# XDS_100_USB_Programmer.net
KiCad netlist of a schematic drawn in Altium Designer
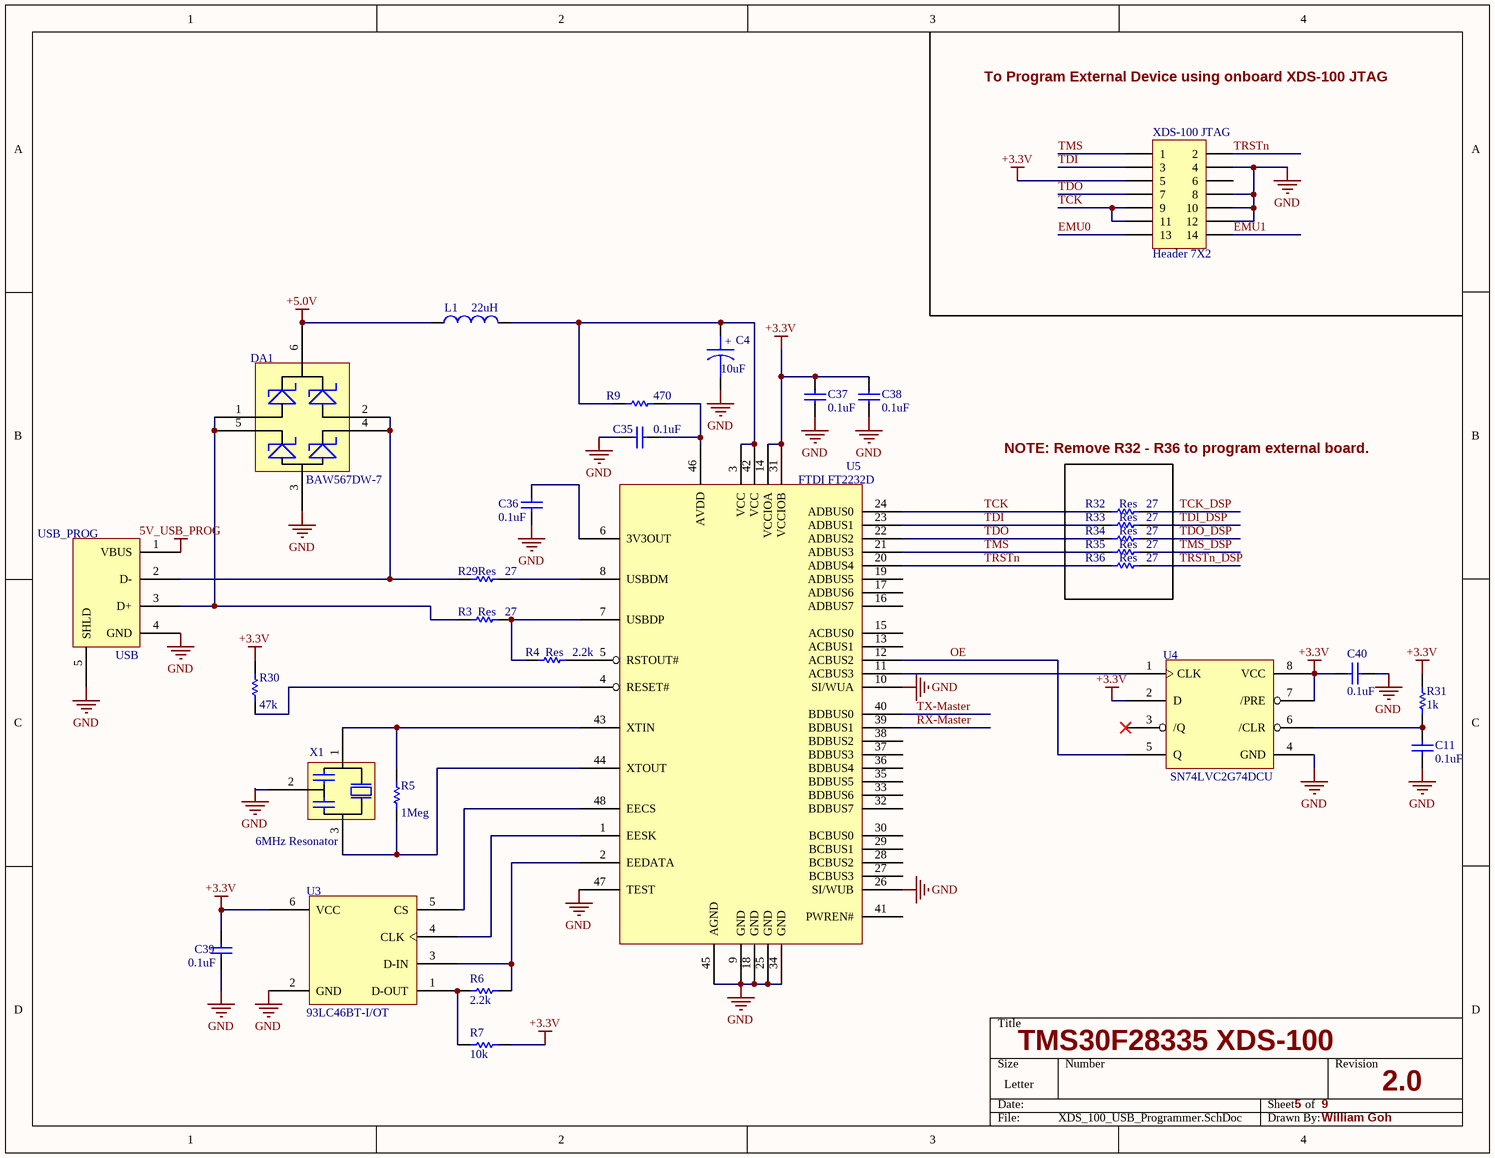
[diagram p0: XDS_100_USB_Programmer.SchDoc]

(export (version "E")
  (design (tool "Eeschema 10.0.6"))
  (components
    (comp (ref "C4")
      (value "10uF")
      (footprint "3528")
      (description "Capacitor Tantalum")
      (fields (field (name "Comment") "Pol Cap"))
      (libsource (lib "F28335_DSC_Breakout") (part "CAPACITOR POL"))
    )
    (comp (ref "C11")
      (value "0.1uF")
      (footprint "0805")
      (description "Capacitor (Semiconductor SIM Model)")
      (fields (field (name "Comment") "Cap Semi") (field (name "PUBLISHER") "Altium Limited"))
      (libsource (lib "F28335_DSC_Breakout") (part "Cap Semi"))
    )
    (comp (ref "C35")
      (value "0.1uF")
      (footprint "0805")
      (description "Capacitor (Semiconductor SIM Model)")
      (fields (field (name "Comment") "Cap Semi") (field (name "PUBLISHER") "Altium Limited"))
      (libsource (lib "F28335_DSC_Breakout") (part "Cap Semi"))
    )
    (comp (ref "C36")
      (value "0.1uF")
      (footprint "0805")
      (description "Capacitor (Semiconductor SIM Model)")
      (fields (field (name "Comment") "Cap Semi") (field (name "PUBLISHER") "Altium Limited"))
      (libsource (lib "F28335_DSC_Breakout") (part "Cap Semi"))
    )
    (comp (ref "C37")
      (value "0.1uF")
      (footprint "0805")
      (description "Capacitor (Semiconductor SIM Model)")
      (fields (field (name "Comment") "Cap Semi") (field (name "PUBLISHER") "Altium Limited"))
      (libsource (lib "F28335_DSC_Breakout") (part "Cap Semi"))
    )
    (comp (ref "C38")
      (value "0.1uF")
      (footprint "0805")
      (description "Capacitor (Semiconductor SIM Model)")
      (fields (field (name "Comment") "Cap Semi") (field (name "PUBLISHER") "Altium Limited"))
      (libsource (lib "F28335_DSC_Breakout") (part "Cap Semi"))
    )
    (comp (ref "C39")
      (value "0.1uF")
      (footprint "0805")
      (description "Capacitor (Semiconductor SIM Model)")
      (fields (field (name "Comment") "Cap Semi") (field (name "PUBLISHER") "Altium Limited"))
      (libsource (lib "F28335_DSC_Breakout") (part "Cap Semi"))
    )
    (comp (ref "C40")
      (value "0.1uF")
      (footprint "0805")
      (description "Capacitor (Semiconductor SIM Model)")
      (fields (field (name "Comment") "Cap Semi") (field (name "PUBLISHER") "Altium Limited"))
      (libsource (lib "F28335_DSC_Breakout") (part "Cap Semi"))
    )
    (comp (ref "DA1")
      (value "BAW567DW-7")
      (footprint "BAW567DW")
      (description "QUAD SURFACE MOUNT SWITCHING DIODE ARRAY")
      (libsource (lib "F28335_DSC_Breakout") (part "BAW567DW-7"))
    )
    (comp (ref "L1")
      (value "22uH")
      (footprint "0805")
      (description "Inductor")
      (fields (field (name "PUBLISHER") "Altium Limited"))
      (libsource (lib "Miscellaneous Devices") (part "Inductor"))
    )
    (comp (ref "R3")
      (value "Res")
      (footprint "0805")
      (description "Semiconductor Resistor")
      (fields (field (name "ALTIUM_VALUE") "27") (field (name "PUBLISHER") "Altium Limited"))
      (libsource (lib "F28335_DSC_Breakout") (part "Res Semi"))
    )
    (comp (ref "R4")
      (value "Res")
      (footprint "0805")
      (description "Semiconductor Resistor")
      (fields (field (name "ALTIUM_VALUE") "2.2k") (field (name "PUBLISHER") "Altium Limited"))
      (libsource (lib "F28335_DSC_Breakout") (part "Res Semi"))
    )
    (comp (ref "R5")
      (value "1Meg")
      (footprint "0805")
      (description "Semiconductor Resistor")
      (fields (field (name "Comment") "Res") (field (name "PUBLISHER") "Altium Limited"))
      (libsource (lib "F28335_DSC_Breakout") (part "Res Semi"))
    )
    (comp (ref "R6")
      (value "2.2k")
      (footprint "0805")
      (description "Semiconductor Resistor")
      (fields (field (name "Comment") "Res") (field (name "PUBLISHER") "Altium Limited"))
      (libsource (lib "F28335_DSC_Breakout") (part "Res Semi"))
    )
    (comp (ref "R7")
      (value "10k")
      (footprint "0805")
      (description "Semiconductor Resistor")
      (fields (field (name "Comment") "Res") (field (name "PUBLISHER") "Altium Limited"))
      (libsource (lib "F28335_DSC_Breakout") (part "Res Semi"))
    )
    (comp (ref "R9")
      (value "470")
      (footprint "0805")
      (description "Semiconductor Resistor")
      (fields (field (name "Comment") "Res") (field (name "PUBLISHER") "Altium Limited"))
      (libsource (lib "F28335_DSC_Breakout") (part "Res Semi"))
    )
    (comp (ref "R29")
      (value "Res")
      (footprint "0805")
      (description "Semiconductor Resistor")
      (fields (field (name "ALTIUM_VALUE") "27") (field (name "PUBLISHER") "Altium Limited"))
      (libsource (lib "F28335_DSC_Breakout") (part "Res Semi"))
    )
    (comp (ref "R30")
      (value "47k")
      (footprint "0805")
      (description "Semiconductor Resistor")
      (fields (field (name "Comment") "Res") (field (name "PUBLISHER") "Altium Limited"))
      (libsource (lib "F28335_DSC_Breakout") (part "Res Semi"))
    )
    (comp (ref "R31")
      (value "1k")
      (footprint "0805")
      (description "Semiconductor Resistor")
      (fields (field (name "Comment") "Res") (field (name "PUBLISHER") "Altium Limited"))
      (libsource (lib "F28335_DSC_Breakout") (part "Res Semi"))
    )
    (comp (ref "R32")
      (value "Res")
      (footprint "0805")
      (description "Semiconductor Resistor")
      (fields (field (name "ALTIUM_VALUE") "27") (field (name "PUBLISHER") "Altium Limited"))
      (libsource (lib "F28335_DSC_Breakout") (part "Res Semi"))
    )
    (comp (ref "R33")
      (value "Res")
      (footprint "0805")
      (description "Semiconductor Resistor")
      (fields (field (name "ALTIUM_VALUE") "27") (field (name "PUBLISHER") "Altium Limited"))
      (libsource (lib "F28335_DSC_Breakout") (part "Res Semi"))
    )
    (comp (ref "R34")
      (value "Res")
      (footprint "0805")
      (description "Semiconductor Resistor")
      (fields (field (name "ALTIUM_VALUE") "27") (field (name "PUBLISHER") "Altium Limited"))
      (libsource (lib "F28335_DSC_Breakout") (part "Res Semi"))
    )
    (comp (ref "R35")
      (value "Res")
      (footprint "0805")
      (description "Semiconductor Resistor")
      (fields (field (name "ALTIUM_VALUE") "27") (field (name "PUBLISHER") "Altium Limited"))
      (libsource (lib "F28335_DSC_Breakout") (part "Res Semi"))
    )
    (comp (ref "R36")
      (value "Res")
      (footprint "0805")
      (description "Semiconductor Resistor")
      (fields (field (name "ALTIUM_VALUE") "27") (field (name "PUBLISHER") "Altium Limited"))
      (libsource (lib "F28335_DSC_Breakout") (part "Res Semi"))
    )
    (comp (ref "U3")
      (value "93LC46BT-I/OT")
      (footprint "93LC46BT-I/OT")
      (description "1K Microwire Compatible Serial EEPROM")
      (libsource (lib "F28335_DSC_Breakout") (part "93LC46BT-I/OT"))
    )
    (comp (ref "U4")
      (value "SN74LVC2G74DCU")
      (footprint "DCU8")
      (description "Single Positive-Edge-Triggered D-Type Flip-Flop with Clear and Preset")
      (libsource (lib "F28335_DSC_Breakout") (part "LVC2G74"))
    )
    (comp (ref "U5")
      (value "FTDI FT2232D")
      (footprint "FTDI FT2232D")
      (libsource (lib "F28335_DSC_Breakout") (part "FTDI FT2232D"))
    )
    (comp (ref "USB_PROG")
      (value "USB")
      (footprint "USB_TypeB_RightAngle")
      (libsource (lib "F28335_DSC_Breakout") (part "USB"))
    )
    (comp (ref "X1")
      (value "6MHz Resonator")
      (footprint "6.00Mhz Resonator")
      (description "Ceramic Resonator")
      (libsource (lib "F28335_DSC_Breakout") (part "Resonator Ceramic"))
    )
    (comp (ref "XDS-100 JTAG")
      (value "Header 7X2")
      (footprint "HDR2X7")
      (description "Header, 7-Pin, Dual row")
      (fields (field (name "PUBLISHER") "Altium Limited"))
      (libsource (lib "F28335_DSC_Breakout") (part "Header 7X2"))
    )
  )
  (nets
    (net (code "1") (name "+3.3V") (class "Default")
      (node (ref "C37") (pin "2") (pinfunction "2_2") (pintype "passive"))
      (node (ref "C38") (pin "1") (pinfunction "1_1") (pintype "passive"))
      (node (ref "C39") (pin "2") (pinfunction "2_2") (pintype "passive"))
      (node (ref "C40") (pin "2") (pinfunction "2_2") (pintype "passive"))
      (node (ref "R30") (pin "2") (pinfunction "2_2") (pintype "passive"))
      (node (ref "R31") (pin "2") (pinfunction "2_2") (pintype "passive"))
      (node (ref "R7") (pin "1") (pinfunction "1_1") (pintype "passive"))
      (node (ref "U3") (pin "6") (pinfunction "VCC_6") (pintype "passive"))
      (node (ref "U4") (pin "2") (pinfunction "D_2") (pintype "passive"))
      (node (ref "U4") (pin "7") (pinfunction "/PRE_7") (pintype "passive"))
      (node (ref "U4") (pin "8") (pinfunction "VCC_8") (pintype "passive"))
      (node (ref "U5") (pin "14") (pinfunction "VCCIOA_14") (pintype "passive"))
      (node (ref "U5") (pin "31") (pinfunction "VCCIOB_31") (pintype "passive"))
      (node (ref "XDS-100 JTAG") (pin "5") (pinfunction "5_5") (pintype "passive"))
    )
    (net (code "2") (name "+5.0V") (class "Default")
      (node (ref "DA1") (pin "6") (pintype "passive"))
      (node (ref "L1") (pin "1") (pinfunction "1_1") (pintype "passive"))
    )
    (net (code "3") (name "/EMU0") (class "Default")
      (node (ref "XDS-100 JTAG") (pin "13") (pinfunction "13_13") (pintype "passive"))
    )
    (net (code "4") (name "/EMU1") (class "Default")
      (node (ref "XDS-100 JTAG") (pin "14") (pinfunction "14_14") (pintype "passive"))
    )
    (net (code "5") (name "/OE") (class "Default")
      (node (ref "U4") (pin "5") (pinfunction "Q_5") (pintype "passive"))
      (node (ref "U5") (pin "12") (pinfunction "ACBUS2_12") (pintype "passive"))
    )
    (net (code "6") (name "/RX-Master") (class "Default")
      (node (ref "U5") (pin "39") (pinfunction "BDBUS1_39") (pintype "passive"))
    )
    (net (code "7") (name "/TCK") (class "Default")
      (node (ref "R32") (pin "1") (pinfunction "1_1") (pintype "passive"))
      (node (ref "U5") (pin "24") (pinfunction "ADBUS0_24") (pintype "passive"))
      (node (ref "XDS-100 JTAG") (pin "11") (pinfunction "11_11") (pintype "passive"))
      (node (ref "XDS-100 JTAG") (pin "9") (pinfunction "9_9") (pintype "passive"))
    )
    (net (code "8") (name "/TCK_DSP") (class "Default")
      (node (ref "R32") (pin "2") (pinfunction "2_2") (pintype "passive"))
    )
    (net (code "9") (name "/TDI") (class "Default")
      (node (ref "R33") (pin "1") (pinfunction "1_1") (pintype "passive"))
      (node (ref "U5") (pin "23") (pinfunction "ADBUS1_23") (pintype "passive"))
      (node (ref "XDS-100 JTAG") (pin "3") (pinfunction "3_3") (pintype "passive"))
    )
    (net (code "10") (name "/TDI_DSP") (class "Default")
      (node (ref "R33") (pin "2") (pinfunction "2_2") (pintype "passive"))
    )
    (net (code "11") (name "/TDO") (class "Default")
      (node (ref "R34") (pin "1") (pinfunction "1_1") (pintype "passive"))
      (node (ref "U5") (pin "22") (pinfunction "ADBUS2_22") (pintype "passive"))
      (node (ref "XDS-100 JTAG") (pin "7") (pinfunction "7_7") (pintype "passive"))
    )
    (net (code "12") (name "/TDO_DSP") (class "Default")
      (node (ref "R34") (pin "2") (pinfunction "2_2") (pintype "passive"))
    )
    (net (code "13") (name "/TMS") (class "Default")
      (node (ref "R35") (pin "1") (pinfunction "1_1") (pintype "passive"))
      (node (ref "U5") (pin "21") (pinfunction "ADBUS3_21") (pintype "passive"))
      (node (ref "XDS-100 JTAG") (pin "1") (pinfunction "1_1") (pintype "passive"))
    )
    (net (code "14") (name "/TMS_DSP") (class "Default")
      (node (ref "R35") (pin "2") (pinfunction "2_2") (pintype "passive"))
    )
    (net (code "15") (name "/TRSTn") (class "Default")
      (node (ref "R36") (pin "1") (pinfunction "1_1") (pintype "passive"))
      (node (ref "U5") (pin "20") (pinfunction "ADBUS4_20") (pintype "passive"))
      (node (ref "XDS-100 JTAG") (pin "2") (pinfunction "2_2") (pintype "passive"))
    )
    (net (code "16") (name "/TRSTn_DSP") (class "Default")
      (node (ref "R36") (pin "2") (pinfunction "2_2") (pintype "passive"))
    )
    (net (code "17") (name "/TX-Master") (class "Default")
      (node (ref "U5") (pin "40") (pinfunction "BDBUS0_40") (pintype "passive"))
    )
    (net (code "18") (name "5V_USB_PROG") (class "Default")
      (node (ref "USB_PROG") (pin "1") (pinfunction "VBUS_1") (pintype "passive"))
    )
    (net (code "19") (name "GND") (class "Default")
      (node (ref "C11") (pin "2") (pinfunction "2_2") (pintype "passive"))
      (node (ref "C35") (pin "2") (pinfunction "2_2") (pintype "passive"))
      (node (ref "C36") (pin "1") (pinfunction "1_1") (pintype "passive"))
      (node (ref "C37") (pin "1") (pinfunction "1_1") (pintype "passive"))
      (node (ref "C38") (pin "2") (pinfunction "2_2") (pintype "passive"))
      (node (ref "C39") (pin "1") (pinfunction "1_1") (pintype "passive"))
      (node (ref "C4") (pin "2") (pinfunction "2_2") (pintype "passive"))
      (node (ref "C40") (pin "1") (pinfunction "1_1") (pintype "passive"))
      (node (ref "DA1") (pin "3") (pintype "passive"))
      (node (ref "U3") (pin "2") (pinfunction "GND_2") (pintype "passive"))
      (node (ref "U4") (pin "4") (pinfunction "GND_4") (pintype "passive"))
      (node (ref "U5") (pin "10") (pinfunction "SI/WUA_10") (pintype "passive"))
      (node (ref "U5") (pin "18") (pinfunction "GND_18") (pintype "passive"))
      (node (ref "U5") (pin "25") (pinfunction "GND_25") (pintype "passive"))
      (node (ref "U5") (pin "26") (pinfunction "SI/WUB_26") (pintype "passive"))
      (node (ref "U5") (pin "34") (pinfunction "GND_34") (pintype "passive"))
      (node (ref "U5") (pin "45") (pinfunction "AGND_45") (pintype "passive"))
      (node (ref "U5") (pin "47") (pinfunction "TEST_47") (pintype "passive"))
      (node (ref "U5") (pin "9") (pinfunction "GND_9") (pintype "passive"))
      (node (ref "USB_PROG") (pin "4") (pinfunction "GND_4") (pintype "passive"))
      (node (ref "USB_PROG") (pin "5") (pinfunction "SHLD_5") (pintype "passive"))
      (node (ref "X1") (pin "2") (pinfunction "GND_2") (pintype "passive"))
      (node (ref "XDS-100 JTAG") (pin "10") (pinfunction "10_10") (pintype "passive"))
      (node (ref "XDS-100 JTAG") (pin "12") (pinfunction "12_12") (pintype "passive"))
      (node (ref "XDS-100 JTAG") (pin "4") (pinfunction "4_4") (pintype "passive"))
      (node (ref "XDS-100 JTAG") (pin "8") (pinfunction "8_8") (pintype "passive"))
    )
    (net (code "20") (name "Net-(C4-Pad1)") (class "Default")
      (node (ref "C4") (pin "1") (pinfunction "1_1") (pintype "passive"))
      (node (ref "L1") (pin "2") (pinfunction "2_2") (pintype "passive"))
      (node (ref "R9") (pin "2") (pinfunction "2_2") (pintype "passive"))
      (node (ref "U5") (pin "3") (pinfunction "VCC_3") (pintype "passive"))
      (node (ref "U5") (pin "42") (pinfunction "VCC_42") (pintype "passive"))
    )
    (net (code "21") (name "Net-(U3-CLK)") (class "Default")
      (node (ref "U3") (pin "4") (pinfunction "CLK_4") (pintype "passive"))
      (node (ref "U5") (pin "1") (pinfunction "EESK_1") (pintype "passive"))
    )
    (net (code "22") (name "Net-(U3-CS)") (class "Default")
      (node (ref "U3") (pin "5") (pinfunction "CS_5") (pintype "passive"))
      (node (ref "U5") (pin "48") (pinfunction "EECS_48") (pintype "passive"))
    )
    (net (code "23") (name "Net-(U3-D-IN)") (class "Default")
      (node (ref "R6") (pin "1") (pinfunction "1_1") (pintype "passive"))
      (node (ref "U3") (pin "3") (pinfunction "D-IN_3") (pintype "passive"))
      (node (ref "U5") (pin "2") (pinfunction "EEDATA_2") (pintype "passive"))
    )
    (net (code "24") (name "Net-(U3-D-OUT)") (class "Default")
      (node (ref "R6") (pin "2") (pinfunction "2_2") (pintype "passive"))
      (node (ref "R7") (pin "2") (pinfunction "2_2") (pintype "passive"))
      (node (ref "U3") (pin "1") (pinfunction "D-OUT_1") (pintype "passive"))
    )
    (net (code "25") (name "Net-(U4-CLK)") (class "Default")
      (node (ref "U4") (pin "1") (pinfunction "CLK_1") (pintype "passive"))
      (node (ref "U5") (pin "11") (pinfunction "ACBUS3_11") (pintype "passive"))
    )
    (net (code "26") (name "Net-(U4-{slash}CLR)") (class "Default")
      (node (ref "C11") (pin "1") (pinfunction "1_1") (pintype "passive"))
      (node (ref "R31") (pin "1") (pinfunction "1_1") (pintype "passive"))
      (node (ref "U4") (pin "6") (pinfunction "/CLR_6") (pintype "passive"))
    )
    (net (code "27") (name "Net-(U5-3V3OUT)") (class "Default")
      (node (ref "C36") (pin "2") (pinfunction "2_2") (pintype "passive"))
      (node (ref "U5") (pin "6") (pinfunction "3V3OUT_6") (pintype "passive"))
    )
    (net (code "28") (name "Net-(U5-AVDD)") (class "Default")
      (node (ref "C35") (pin "1") (pinfunction "1_1") (pintype "passive"))
      (node (ref "R9") (pin "1") (pinfunction "1_1") (pintype "passive"))
      (node (ref "U5") (pin "46") (pinfunction "AVDD_46") (pintype "passive"))
    )
    (net (code "29") (name "Net-(U5-RESET#)") (class "Default")
      (node (ref "R30") (pin "1") (pinfunction "1_1") (pintype "passive"))
      (node (ref "U5") (pin "4") (pinfunction "RESET#_4") (pintype "passive"))
    )
    (net (code "30") (name "Net-(U5-RSTOUT#)") (class "Default")
      (node (ref "R4") (pin "2") (pinfunction "2_2") (pintype "passive"))
      (node (ref "U5") (pin "5") (pinfunction "RSTOUT#_5") (pintype "passive"))
    )
    (net (code "31") (name "Net-(U5-USBDM)") (class "Default")
      (node (ref "R29") (pin "2") (pinfunction "2_2") (pintype "passive"))
      (node (ref "U5") (pin "8") (pinfunction "USBDM_8") (pintype "passive"))
    )
    (net (code "32") (name "Net-(U5-USBDP)") (class "Default")
      (node (ref "R3") (pin "2") (pinfunction "2_2") (pintype "passive"))
      (node (ref "R4") (pin "1") (pinfunction "1_1") (pintype "passive"))
      (node (ref "U5") (pin "7") (pinfunction "USBDP_7") (pintype "passive"))
    )
    (net (code "33") (name "Net-(U5-XTIN)") (class "Default")
      (node (ref "R5") (pin "2") (pinfunction "2_2") (pintype "passive"))
      (node (ref "U5") (pin "43") (pinfunction "XTIN_43") (pintype "passive"))
      (node (ref "X1") (pin "1") (pintype "passive"))
    )
    (net (code "34") (name "Net-(U5-XTOUT)") (class "Default")
      (node (ref "R5") (pin "1") (pinfunction "1_1") (pintype "passive"))
      (node (ref "U5") (pin "44") (pinfunction "XTOUT_44") (pintype "passive"))
      (node (ref "X1") (pin "3") (pintype "passive"))
    )
    (net (code "35") (name "Net-(USB_PROG-D+)") (class "Default")
      (node (ref "DA1") (pin "1") (pintype "passive"))
      (node (ref "DA1") (pin "5") (pintype "passive"))
      (node (ref "R3") (pin "1") (pinfunction "1_1") (pintype "passive"))
      (node (ref "USB_PROG") (pin "3") (pinfunction "D+_3") (pintype "passive"))
    )
    (net (code "36") (name "Net-(USB_PROG-D-)") (class "Default")
      (node (ref "DA1") (pin "2") (pintype "passive"))
      (node (ref "DA1") (pin "4") (pintype "passive"))
      (node (ref "R29") (pin "1") (pinfunction "1_1") (pintype "passive"))
      (node (ref "USB_PROG") (pin "2") (pinfunction "D-_2") (pintype "passive"))
    )
    (net (code "37") (name "unconnected-(U4-{slash}Q-Pad3)") (class "Default")
      (node (ref "U4") (pin "3") (pinfunction "/Q_3") (pintype "passive+no_connect"))
    )
    (net (code "38") (name "unconnected-(U5-ACBUS0-Pad15)") (class "Default")
      (node (ref "U5") (pin "15") (pinfunction "ACBUS0_15") (pintype "passive"))
    )
    (net (code "39") (name "unconnected-(U5-ACBUS1-Pad13)") (class "Default")
      (node (ref "U5") (pin "13") (pinfunction "ACBUS1_13") (pintype "passive"))
    )
    (net (code "40") (name "unconnected-(U5-ADBUS5-Pad19)") (class "Default")
      (node (ref "U5") (pin "19") (pinfunction "ADBUS5_19") (pintype "passive"))
    )
    (net (code "41") (name "unconnected-(U5-ADBUS6-Pad17)") (class "Default")
      (node (ref "U5") (pin "17") (pinfunction "ADBUS6_17") (pintype "passive"))
    )
    (net (code "42") (name "unconnected-(U5-ADBUS7-Pad16)") (class "Default")
      (node (ref "U5") (pin "16") (pinfunction "ADBUS7_16") (pintype "passive"))
    )
    (net (code "43") (name "unconnected-(U5-BCBUS0-Pad30)") (class "Default")
      (node (ref "U5") (pin "30") (pinfunction "BCBUS0_30") (pintype "passive"))
    )
    (net (code "44") (name "unconnected-(U5-BCBUS1-Pad29)") (class "Default")
      (node (ref "U5") (pin "29") (pinfunction "BCBUS1_29") (pintype "passive"))
    )
    (net (code "45") (name "unconnected-(U5-BCBUS2-Pad28)") (class "Default")
      (node (ref "U5") (pin "28") (pinfunction "BCBUS2_28") (pintype "passive"))
    )
    (net (code "46") (name "unconnected-(U5-BCBUS3-Pad27)") (class "Default")
      (node (ref "U5") (pin "27") (pinfunction "BCBUS3_27") (pintype "passive"))
    )
    (net (code "47") (name "unconnected-(U5-BDBUS2-Pad38)") (class "Default")
      (node (ref "U5") (pin "38") (pinfunction "BDBUS2_38") (pintype "passive"))
    )
    (net (code "48") (name "unconnected-(U5-BDBUS3-Pad37)") (class "Default")
      (node (ref "U5") (pin "37") (pinfunction "BDBUS3_37") (pintype "passive"))
    )
    (net (code "49") (name "unconnected-(U5-BDBUS4-Pad36)") (class "Default")
      (node (ref "U5") (pin "36") (pinfunction "BDBUS4_36") (pintype "passive"))
    )
    (net (code "50") (name "unconnected-(U5-BDBUS5-Pad35)") (class "Default")
      (node (ref "U5") (pin "35") (pinfunction "BDBUS5_35") (pintype "passive"))
    )
    (net (code "51") (name "unconnected-(U5-BDBUS6-Pad33)") (class "Default")
      (node (ref "U5") (pin "33") (pinfunction "BDBUS6_33") (pintype "passive"))
    )
    (net (code "52") (name "unconnected-(U5-BDBUS7-Pad32)") (class "Default")
      (node (ref "U5") (pin "32") (pinfunction "BDBUS7_32") (pintype "passive"))
    )
    (net (code "53") (name "unconnected-(U5-PWREN#-Pad41)") (class "Default")
      (node (ref "U5") (pin "41") (pinfunction "PWREN#_41") (pintype "passive"))
    )
    (net (code "54") (name "unconnected-(XDS-100 JTAG-Pad6)") (class "Default")
      (node (ref "XDS-100 JTAG") (pin "6") (pinfunction "6_6") (pintype "passive"))
    )
  )
)
